# Fingerprint_lock_1_3.net
KiCad netlist of a schematic drawn in EAGLE
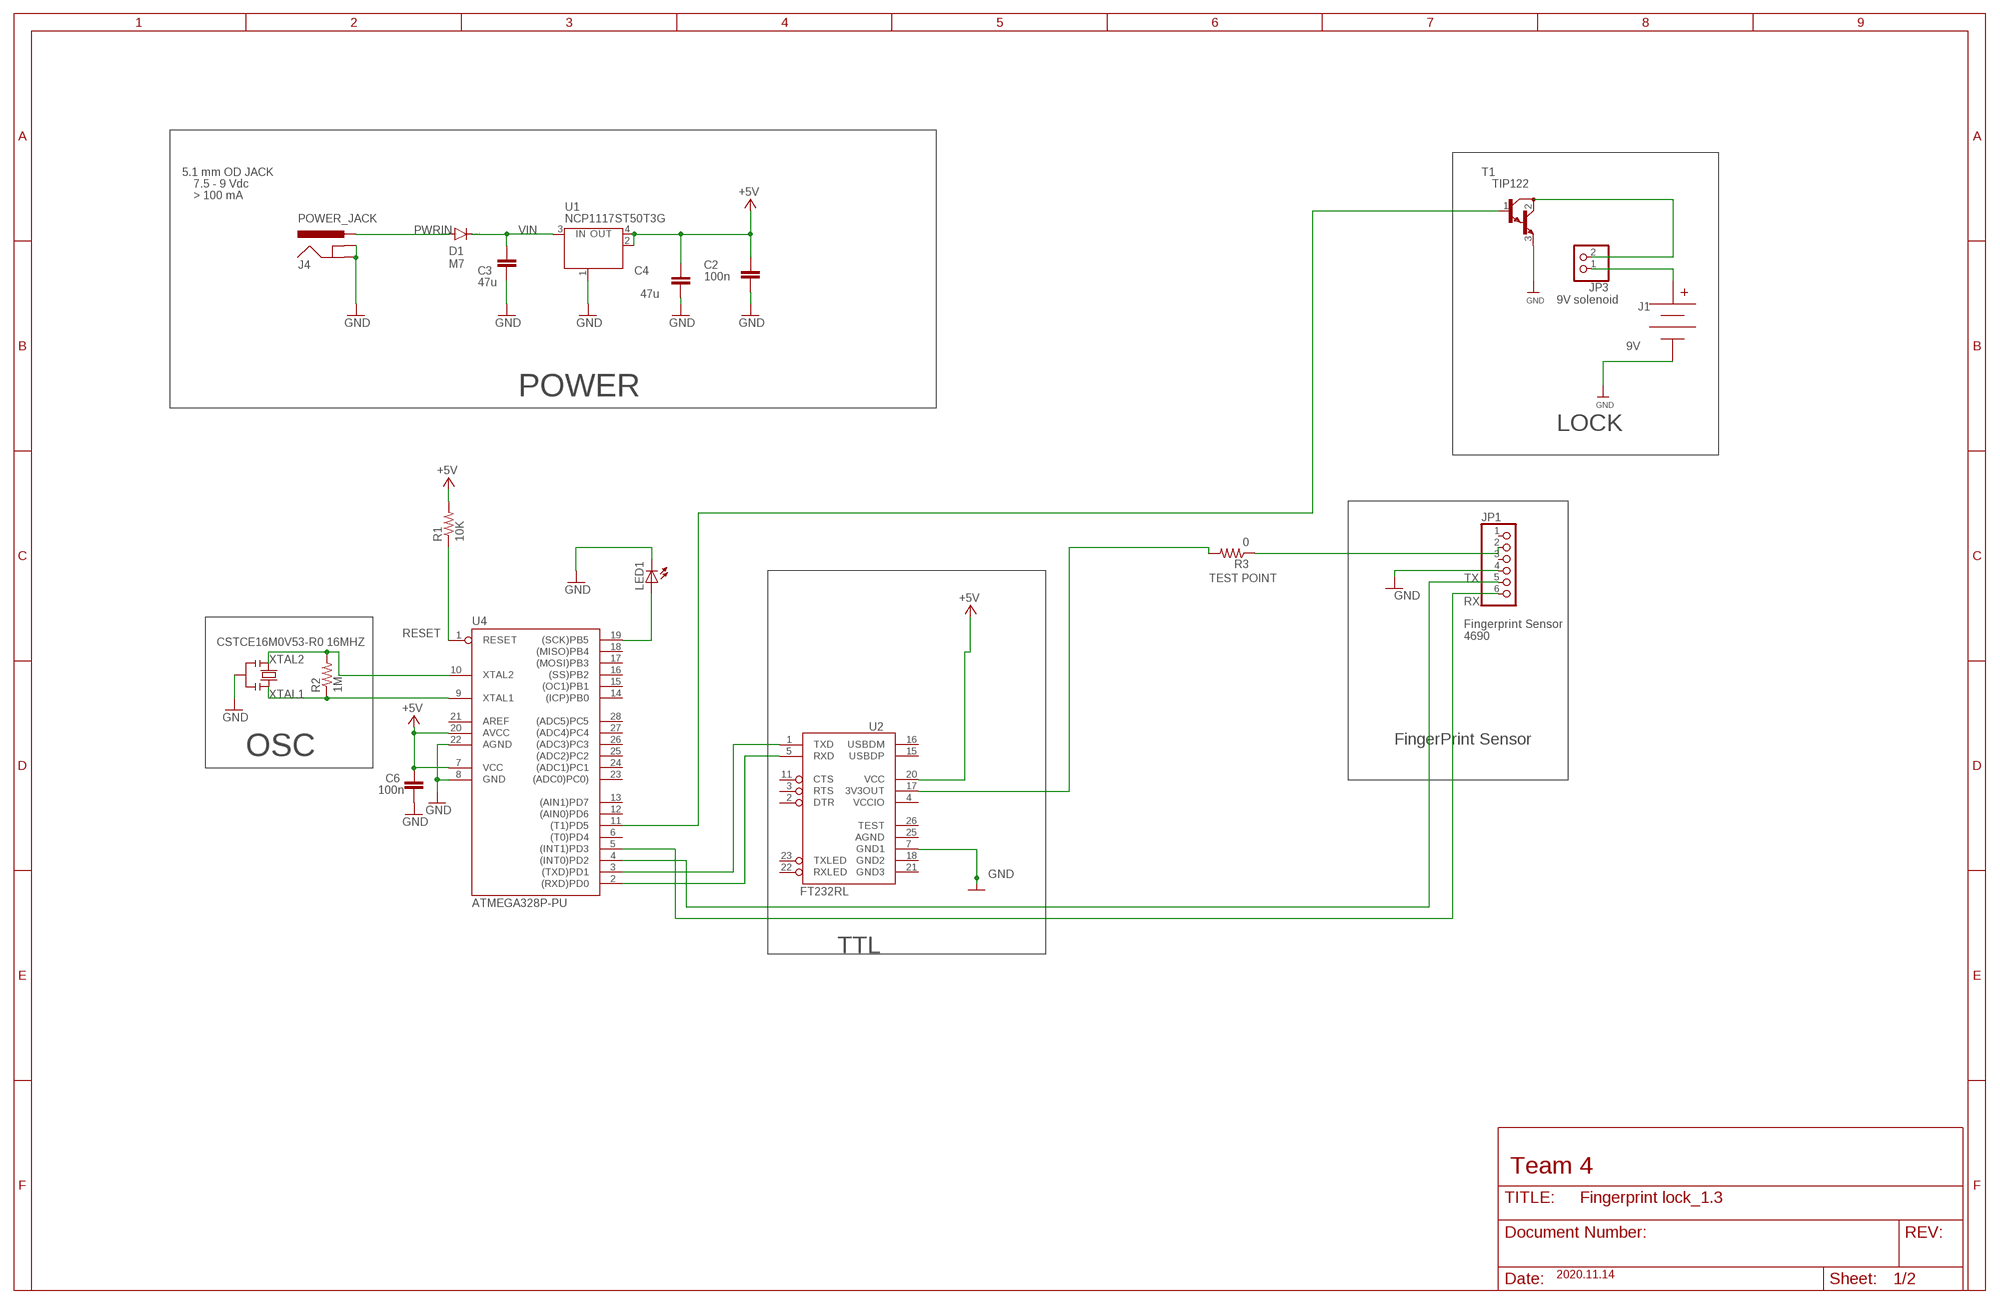
[diagram p0: schematic, sheet 1]

(export (version "E")
  (design (tool "Eeschema 10.0.6"))
  (components
    (comp (ref "C2")
      (value "100n")
      (footprint "eagle-import:C0805")
      (libsource (lib "eagle-import") (part "C-EUC0805"))
    )
    (comp (ref "C3")
      (value "47u")
      (footprint "eagle-import:C0805")
      (libsource (lib "eagle-import") (part "C-EUC0805"))
    )
    (comp (ref "C4")
      (value "47u")
      (footprint "eagle-import:C0805")
      (libsource (lib "eagle-import") (part "C-EUC0805"))
    )
    (comp (ref "C6")
      (value "100n")
      (footprint "eagle-import:C0805")
      (libsource (lib "eagle-import") (part "C-EUC0805"))
    )
    (comp (ref "D1")
      (value "M7")
      (footprint "eagle-import:SMB")
      (libsource (lib "eagle-import") (part "DIODE-SMB"))
    )
    (comp (ref "J1")
      (value "9V")
      (footprint "eagle-import:BC9VPC")
      (libsource (lib "eagle-import") (part "BC9VPC"))
    )
    (comp (ref "J4")
      (value "POWER_JACK")
      (footprint "eagle-import:POWER_JACK_PTH")
      (libsource (lib "eagle-import") (part "POWER_JACK"))
    )
    (comp (ref "JP1")
      (value "PINHD-1X6B")
      (footprint "eagle-import:1X06-BIG")
      (libsource (lib "eagle-import") (part "PINHD-1X6B"))
    )
    (comp (ref "JP3")
      (value "PINHD-1X2")
      (footprint "eagle-import:1X02")
      (libsource (lib "eagle-import") (part "PINHD-1X2"))
    )
    (comp (ref "LED1")
      (value "LEDB155")
      (footprint "eagle-import:Q62902-B155")
      (libsource (lib "eagle-import") (part "LEDB155"))
    )
    (comp (ref "R1")
      (value "10K")
      (footprint "eagle-import:R0805")
      (libsource (lib "eagle-import") (part "R-US_R0805"))
    )
    (comp (ref "R2")
      (value "1M")
      (footprint "eagle-import:R0805")
      (libsource (lib "eagle-import") (part "R-US_R0805"))
    )
    (comp (ref "R3")
      (value "0")
      (footprint "eagle-import:R0805")
      (libsource (lib "eagle-import") (part "R-US_R0805"))
    )
    (comp (ref "T1")
      (value "TIP122")
      (footprint "eagle-import:TO220")
      (libsource (lib "eagle-import") (part "TIP122"))
    )
    (comp (ref "U1")
      (value "NCP1117ST50T3G")
      (footprint "eagle-import:SOT223")
      (libsource (lib "eagle-import") (part "MC33269ST-3.3T3"))
    )
    (comp (ref "U2")
      (value "FT232RL")
      (footprint "eagle-import:SSOP28DB")
      (libsource (lib "eagle-import") (part "FT232RL-BASICSSOP"))
    )
    (comp (ref "U4")
      (value "ATMEGA328P-PU")
      (footprint "eagle-import:DIL28-3")
      (libsource (lib "eagle-import") (part "ATMEGA328P-PU"))
    )
    (comp (ref "X1")
      (value "CSTCE16M0V53-R0 16MHZ")
      (footprint "eagle-import:RESONATOR")
      (libsource (lib "eagle-import") (part "RESONATORMU"))
    )
  )
  (nets
    (net (code "1") (name "+5V") (class "Default")
      (node (ref "C2") (pin "2") (pinfunction "2_2") (pintype "passive"))
      (node (ref "C4") (pin "2") (pinfunction "2_2") (pintype "passive"))
      (node (ref "C6") (pin "2") (pinfunction "2_2") (pintype "passive"))
      (node (ref "R1") (pin "2") (pinfunction "2_2") (pintype "passive"))
      (node (ref "U1") (pin "2") (pinfunction "OUT_2") (pintype "passive"))
      (node (ref "U1") (pin "4") (pinfunction "OUT_4") (pintype "passive"))
      (node (ref "U2") (pin "20") (pinfunction "VCC_20") (pintype "power_in"))
      (node (ref "U4") (pin "20") (pinfunction "AVCC_20") (pintype "power_in"))
      (node (ref "U4") (pin "7") (pinfunction "VCC_7") (pintype "power_in"))
    )
    (net (code "2") (name "AGND") (class "Default")
      (node (ref "U2") (pin "25") (pinfunction "AGND_25") (pintype "power_in"))
    )
    (net (code "3") (name "GND") (class "Default")
      (node (ref "C2") (pin "1") (pinfunction "1_1") (pintype "passive"))
      (node (ref "C3") (pin "1") (pinfunction "1_1") (pintype "passive"))
      (node (ref "C4") (pin "1") (pinfunction "1_1") (pintype "passive"))
      (node (ref "C6") (pin "1") (pinfunction "1_1") (pintype "passive"))
      (node (ref "J1") (pin "V-") (pinfunction "V-_V-") (pintype "bidirectional"))
      (node (ref "J4") (pin "GND") (pinfunction "GND_GND") (pintype "bidirectional"))
      (node (ref "J4") (pin "GNDBREAK") (pinfunction "GNDBREAK_GNDBREAK") (pintype "bidirectional"))
      (node (ref "JP1") (pin "4") (pinfunction "4_4") (pintype "passive"))
      (node (ref "LED1") (pin "K") (pinfunction "C_K") (pintype "passive"))
      (node (ref "T1") (pin "3") (pinfunction "E_3") (pintype "passive"))
      (node (ref "U1") (pin "1") (pinfunction "GND/ADJ_1") (pintype "input"))
      (node (ref "U2") (pin "7") (pinfunction "GND1_7") (pintype "power_in"))
      (node (ref "U4") (pin "22") (pinfunction "AGND_22") (pintype "power_in"))
      (node (ref "U4") (pin "8") (pinfunction "GND_8") (pintype "power_in"))
      (node (ref "X1") (pin "2") (pinfunction "2_2") (pintype "passive"))
    )
    (net (code "4") (name "GND2") (class "Default")
      (node (ref "U2") (pin "18") (pinfunction "GND2_18") (pintype "power_in"))
    )
    (net (code "5") (name "GND3") (class "Default")
      (node (ref "U2") (pin "21") (pinfunction "GND3_21") (pintype "power_in"))
    )
    (net (code "6") (name "Net-(J1-PadV+)") (class "Default")
      (node (ref "J1") (pin "V+") (pinfunction "V+_V+") (pintype "bidirectional"))
      (node (ref "JP3") (pin "1") (pinfunction "1_1") (pintype "passive"))
    )
    (net (code "7") (name "Net-(JP1-Pad2)") (class "Default")
      (node (ref "JP1") (pin "2") (pinfunction "2_2") (pintype "passive"))
      (node (ref "R3") (pin "1") (pinfunction "1_1") (pintype "passive"))
    )
    (net (code "8") (name "Net-(T1-B)") (class "Default")
      (node (ref "T1") (pin "1") (pinfunction "B_1") (pintype "passive"))
      (node (ref "U4") (pin "11") (pinfunction "(T1)PD5_11") (pintype "bidirectional"))
    )
    (net (code "9") (name "Net-(T1-C)") (class "Default")
      (node (ref "JP3") (pin "2") (pinfunction "2_2") (pintype "passive"))
      (node (ref "T1") (pin "2") (pinfunction "C_2") (pintype "passive"))
    )
    (net (code "10") (name "Net-(U2-3V3OUT)") (class "Default")
      (node (ref "R3") (pin "2") (pinfunction "2_2") (pintype "passive"))
      (node (ref "U2") (pin "17") (pinfunction "3V3OUT_17") (pintype "output"))
    )
    (net (code "11") (name "Net-(U2-RXD)") (class "Default")
      (node (ref "U2") (pin "5") (pinfunction "RXD_5") (pintype "input"))
      (node (ref "U4") (pin "2") (pinfunction "(RXD)PD0_2") (pintype "bidirectional"))
    )
    (net (code "12") (name "Net-(U2-TXD)") (class "Default")
      (node (ref "U2") (pin "1") (pinfunction "TXD_1") (pintype "output"))
      (node (ref "U4") (pin "3") (pinfunction "(TXD)PD1_3") (pintype "bidirectional"))
    )
    (net (code "13") (name "Net-(U4-(INT0)PD2)") (class "Default")
      (node (ref "JP1") (pin "5") (pinfunction "5_5") (pintype "passive"))
      (node (ref "U4") (pin "4") (pinfunction "(INT0)PD2_4") (pintype "bidirectional"))
    )
    (net (code "14") (name "Net-(U4-(INT1)PD3)") (class "Default")
      (node (ref "JP1") (pin "6") (pinfunction "6_6") (pintype "passive"))
      (node (ref "U4") (pin "5") (pinfunction "(INT1)PD3_5") (pintype "bidirectional"))
    )
    (net (code "15") (name "Net-(U4-(SCK)PB5)") (class "Default")
      (node (ref "LED1") (pin "A") (pinfunction "A_A") (pintype "passive"))
      (node (ref "U4") (pin "19") (pinfunction "(SCK)PB5_19") (pintype "bidirectional"))
    )
    (net (code "16") (name "PWRIN") (class "Default")
      (node (ref "D1") (pin "A") (pinfunction "A_A") (pintype "passive"))
      (node (ref "J4") (pin "PWR") (pinfunction "PWR_PWR") (pintype "bidirectional"))
    )
    (net (code "17") (name "RESET") (class "Default")
      (node (ref "R1") (pin "1") (pinfunction "1_1") (pintype "passive"))
      (node (ref "U4") (pin "1") (pinfunction "RESET_1") (pintype "input"))
    )
    (net (code "18") (name "VCCIO") (class "Default")
      (node (ref "U2") (pin "4") (pinfunction "VCCIO_4") (pintype "power_in"))
    )
    (net (code "19") (name "VIN") (class "Default")
      (node (ref "C3") (pin "2") (pinfunction "2_2") (pintype "passive"))
      (node (ref "D1") (pin "C") (pinfunction "C_C") (pintype "passive"))
      (node (ref "U1") (pin "3") (pinfunction "IN_3") (pintype "input"))
    )
    (net (code "20") (name "XTAL1") (class "Default")
      (node (ref "R2") (pin "1") (pinfunction "1_1") (pintype "passive"))
      (node (ref "U4") (pin "9") (pinfunction "XTAL1_9") (pintype "bidirectional"))
      (node (ref "X1") (pin "3") (pinfunction "3_3") (pintype "passive"))
    )
    (net (code "21") (name "XTAL2") (class "Default")
      (node (ref "R2") (pin "2") (pinfunction "2_2") (pintype "passive"))
      (node (ref "U4") (pin "10") (pinfunction "XTAL2_10") (pintype "bidirectional"))
      (node (ref "X1") (pin "1") (pinfunction "1_1") (pintype "passive"))
    )
    (net (code "22") (name "unconnected-(JP1-Pad1)") (class "Default")
      (node (ref "JP1") (pin "1") (pinfunction "1_1") (pintype "passive"))
    )
    (net (code "23") (name "unconnected-(JP1-Pad3)") (class "Default")
      (node (ref "JP1") (pin "3") (pinfunction "3_3") (pintype "passive"))
    )
    (net (code "24") (name "unconnected-(U2-CTS-Pad11)") (class "Default")
      (node (ref "U2") (pin "11") (pinfunction "CTS_11") (pintype "bidirectional"))
    )
    (net (code "25") (name "unconnected-(U2-DTR-Pad2)") (class "Default")
      (node (ref "U2") (pin "2") (pinfunction "DTR_2") (pintype "bidirectional"))
    )
    (net (code "26") (name "unconnected-(U2-RTS-Pad3)") (class "Default")
      (node (ref "U2") (pin "3") (pinfunction "RTS_3") (pintype "bidirectional"))
    )
    (net (code "27") (name "unconnected-(U2-RXLED-Pad22)") (class "Default")
      (node (ref "U2") (pin "22") (pinfunction "RXLED_22") (pintype "bidirectional"))
    )
    (net (code "28") (name "unconnected-(U2-TEST-Pad26)") (class "Default")
      (node (ref "U2") (pin "26") (pinfunction "TEST_26") (pintype "input"))
    )
    (net (code "29") (name "unconnected-(U2-TXLED-Pad23)") (class "Default")
      (node (ref "U2") (pin "23") (pinfunction "TXLED_23") (pintype "bidirectional"))
    )
    (net (code "30") (name "unconnected-(U2-USBDM-Pad16)") (class "Default")
      (node (ref "U2") (pin "16") (pinfunction "USBDM_16") (pintype "bidirectional"))
    )
    (net (code "31") (name "unconnected-(U2-USBDP-Pad15)") (class "Default")
      (node (ref "U2") (pin "15") (pinfunction "USBDP_15") (pintype "bidirectional"))
    )
    (net (code "32") (name "unconnected-(U4-(ADC0)PC0)-Pad23)") (class "Default")
      (node (ref "U4") (pin "23") (pinfunction "(ADC0)PC0)_23") (pintype "bidirectional"))
    )
    (net (code "33") (name "unconnected-(U4-(ADC1)PC1-Pad24)") (class "Default")
      (node (ref "U4") (pin "24") (pinfunction "(ADC1)PC1_24") (pintype "bidirectional"))
    )
    (net (code "34") (name "unconnected-(U4-(ADC2)PC2-Pad25)") (class "Default")
      (node (ref "U4") (pin "25") (pinfunction "(ADC2)PC2_25") (pintype "bidirectional"))
    )
    (net (code "35") (name "unconnected-(U4-(ADC3)PC3-Pad26)") (class "Default")
      (node (ref "U4") (pin "26") (pinfunction "(ADC3)PC3_26") (pintype "bidirectional"))
    )
    (net (code "36") (name "unconnected-(U4-(ADC4)PC4-Pad27)") (class "Default")
      (node (ref "U4") (pin "27") (pinfunction "(ADC4)PC4_27") (pintype "bidirectional"))
    )
    (net (code "37") (name "unconnected-(U4-(ADC5)PC5-Pad28)") (class "Default")
      (node (ref "U4") (pin "28") (pinfunction "(ADC5)PC5_28") (pintype "bidirectional"))
    )
    (net (code "38") (name "unconnected-(U4-(AIN0)PD6-Pad12)") (class "Default")
      (node (ref "U4") (pin "12") (pinfunction "(AIN0)PD6_12") (pintype "bidirectional"))
    )
    (net (code "39") (name "unconnected-(U4-(AIN1)PD7-Pad13)") (class "Default")
      (node (ref "U4") (pin "13") (pinfunction "(AIN1)PD7_13") (pintype "bidirectional"))
    )
    (net (code "40") (name "unconnected-(U4-(ICP)PB0-Pad14)") (class "Default")
      (node (ref "U4") (pin "14") (pinfunction "(ICP)PB0_14") (pintype "bidirectional"))
    )
    (net (code "41") (name "unconnected-(U4-(MISO)PB4-Pad18)") (class "Default")
      (node (ref "U4") (pin "18") (pinfunction "(MISO)PB4_18") (pintype "bidirectional"))
    )
    (net (code "42") (name "unconnected-(U4-(MOSI)PB3-Pad17)") (class "Default")
      (node (ref "U4") (pin "17") (pinfunction "(MOSI)PB3_17") (pintype "bidirectional"))
    )
    (net (code "43") (name "unconnected-(U4-(OC1)PB1-Pad15)") (class "Default")
      (node (ref "U4") (pin "15") (pinfunction "(OC1)PB1_15") (pintype "bidirectional"))
    )
    (net (code "44") (name "unconnected-(U4-(SS)PB2-Pad16)") (class "Default")
      (node (ref "U4") (pin "16") (pinfunction "(SS)PB2_16") (pintype "bidirectional"))
    )
    (net (code "45") (name "unconnected-(U4-(T0)PD4-Pad6)") (class "Default")
      (node (ref "U4") (pin "6") (pinfunction "(T0)PD4_6") (pintype "bidirectional"))
    )
    (net (code "46") (name "unconnected-(U4-AREF-Pad21)") (class "Default")
      (node (ref "U4") (pin "21") (pinfunction "AREF_21") (pintype "passive"))
    )
  )
)
